# displayBoard-v1.net
KiCad netlist of a schematic drawn in EAGLE
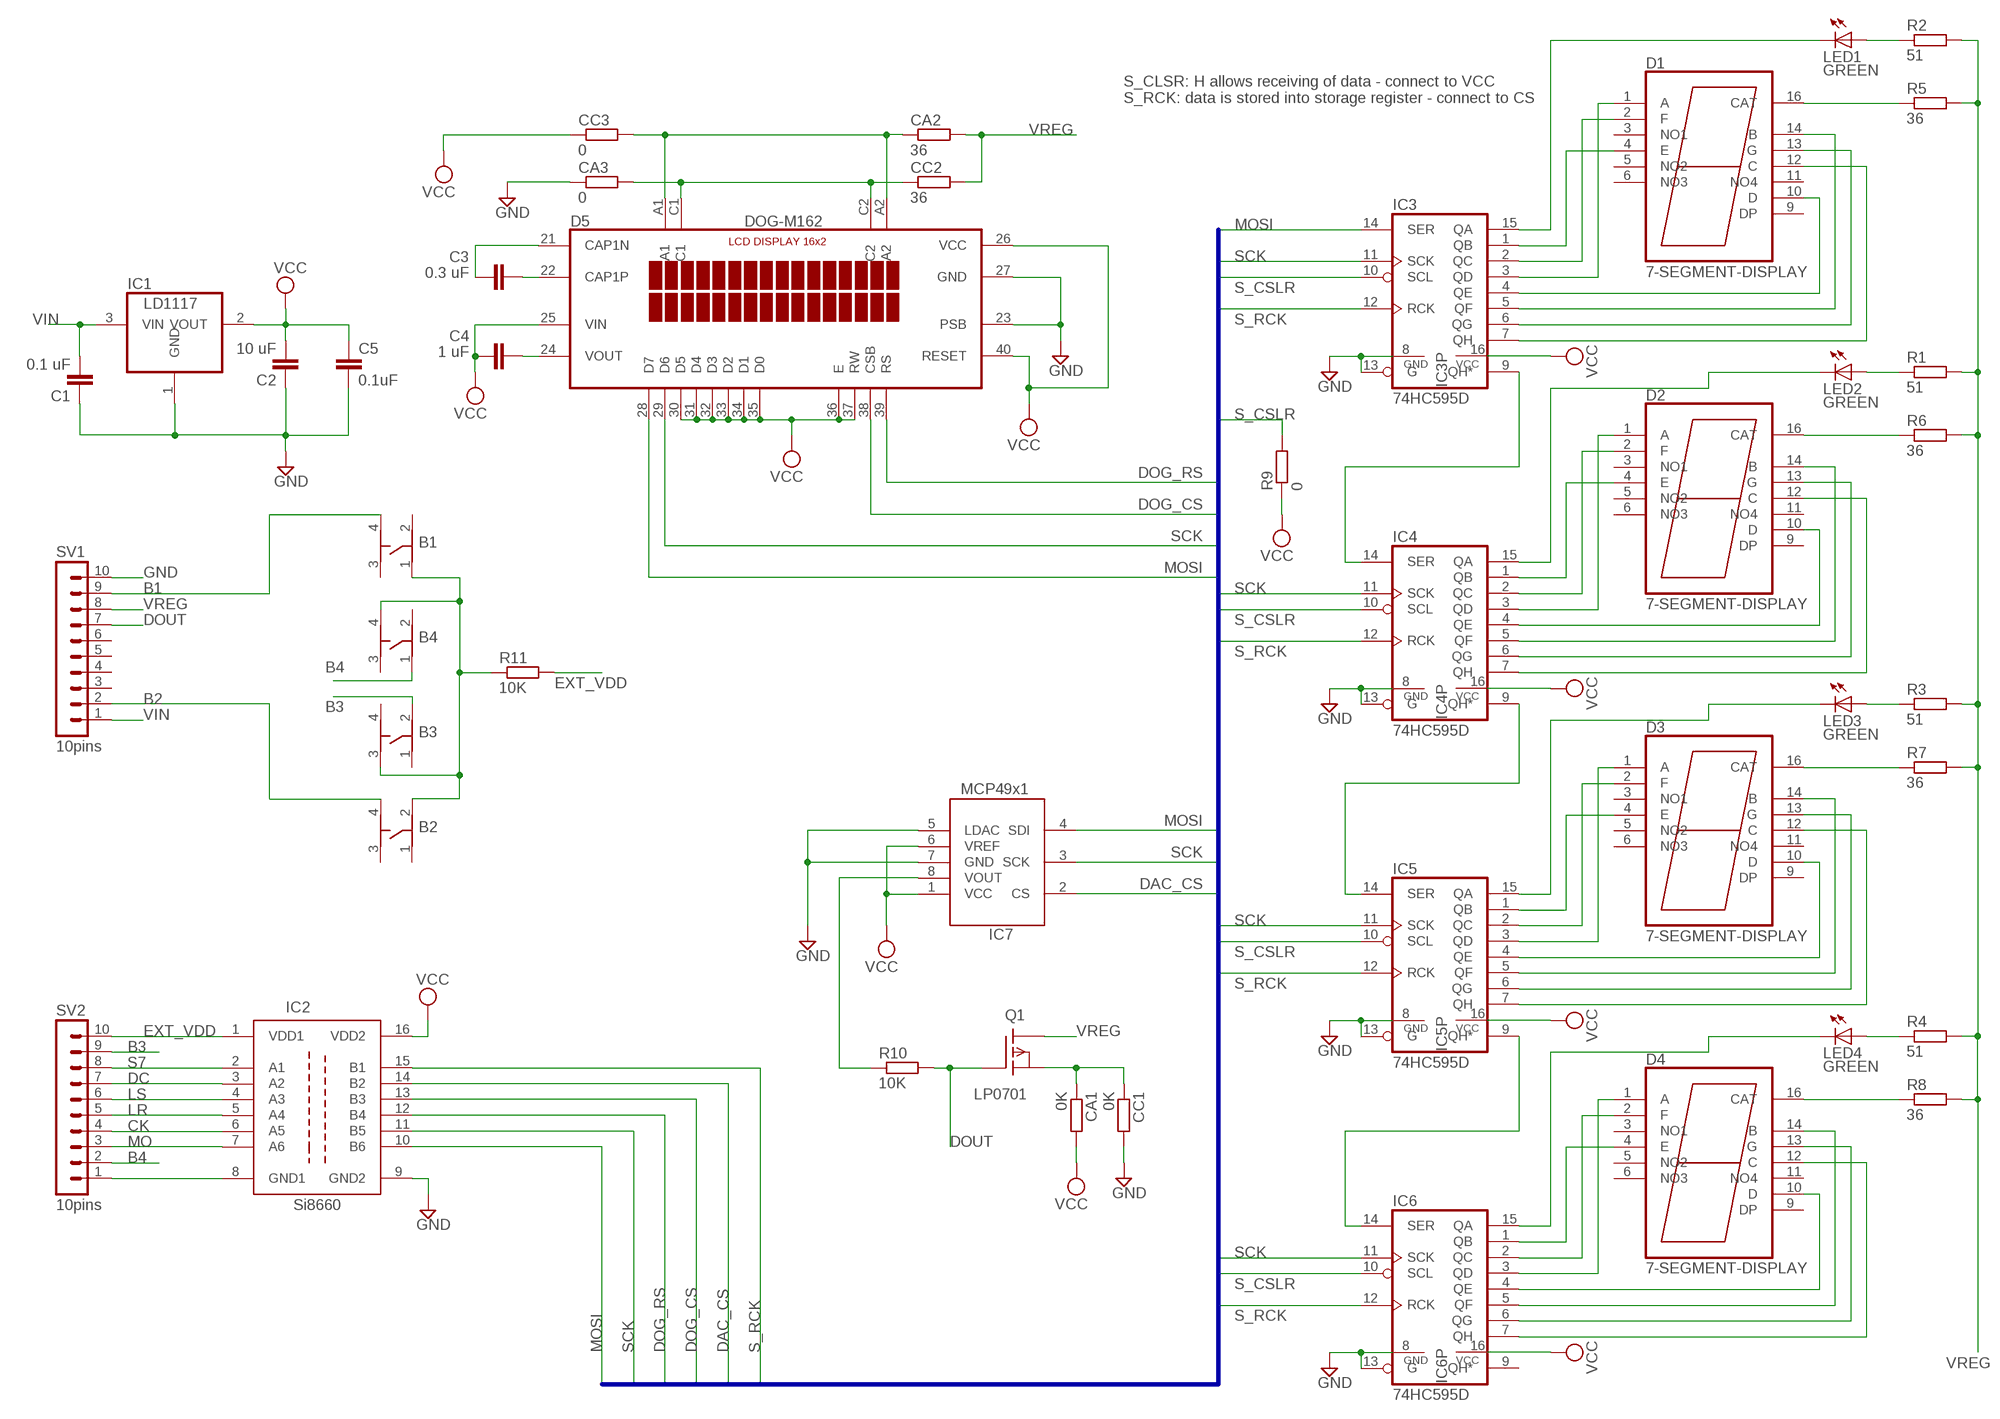
[diagram p0: schematic, sheet 1]

(export (version "E")
  (design (tool "Eeschema 10.0.6"))
  (components
    (comp (ref "B1")
      (value "BUTTON-D6X")
      (footprint "eagle-import:BUTTON-D6X")
      (libsource (lib "eagle-import") (part "BUTTON-D6X"))
    )
    (comp (ref "B2")
      (value "BUTTON-D6X")
      (footprint "eagle-import:BUTTON-D6X")
      (libsource (lib "eagle-import") (part "BUTTON-D6X"))
    )
    (comp (ref "B3")
      (value "BUTTON-D6X")
      (footprint "eagle-import:BUTTON-D6X")
      (libsource (lib "eagle-import") (part "BUTTON-D6X"))
    )
    (comp (ref "B4")
      (value "BUTTON-D6X")
      (footprint "eagle-import:BUTTON-D6X")
      (libsource (lib "eagle-import") (part "BUTTON-D6X"))
    )
    (comp (ref "C1")
      (value "0.1 uF")
      (footprint "eagle-import:C1206")
      (libsource (lib "eagle-import") (part "C-EUC1206"))
    )
    (comp (ref "C2")
      (value "10 uF")
      (footprint "eagle-import:C1206")
      (libsource (lib "eagle-import") (part "C-EUC1206"))
    )
    (comp (ref "C3")
      (value "0.3 uF")
      (footprint "eagle-import:C1206")
      (libsource (lib "eagle-import") (part "C-EUC1206"))
    )
    (comp (ref "C4")
      (value "1 uF")
      (footprint "eagle-import:C1206")
      (libsource (lib "eagle-import") (part "C-EUC1206"))
    )
    (comp (ref "C5")
      (value "0.1uF")
      (footprint "eagle-import:C1206")
      (libsource (lib "eagle-import") (part "C-EUC1206"))
    )
    (comp (ref "CA1")
      (value "0K")
      (footprint "eagle-import:R1206")
      (libsource (lib "eagle-import") (part "R-EU_R1206"))
    )
    (comp (ref "CA2")
      (value "36")
      (footprint "eagle-import:R1206")
      (libsource (lib "eagle-import") (part "R-EU_R1206"))
    )
    (comp (ref "CA3")
      (value "0")
      (footprint "eagle-import:R1206")
      (libsource (lib "eagle-import") (part "R-EU_R1206"))
    )
    (comp (ref "CC1")
      (value "0K")
      (footprint "eagle-import:R1206")
      (libsource (lib "eagle-import") (part "R-EU_R1206"))
    )
    (comp (ref "CC2")
      (value "36")
      (footprint "eagle-import:R1206")
      (libsource (lib "eagle-import") (part "R-EU_R1206"))
    )
    (comp (ref "CC3")
      (value "0")
      (footprint "eagle-import:R1206")
      (libsource (lib "eagle-import") (part "R-EU_R1206"))
    )
    (comp (ref "D1")
      (value "7-SEGMENT-DISPLAY")
      (footprint "eagle-import:LDS-A812")
      (libsource (lib "eagle-import") (part "7-SEGMENT-DISPLAY"))
    )
    (comp (ref "D2")
      (value "7-SEGMENT-DISPLAY")
      (footprint "eagle-import:LDS-A812")
      (libsource (lib "eagle-import") (part "7-SEGMENT-DISPLAY"))
    )
    (comp (ref "D3")
      (value "7-SEGMENT-DISPLAY")
      (footprint "eagle-import:LDS-A812")
      (libsource (lib "eagle-import") (part "7-SEGMENT-DISPLAY"))
    )
    (comp (ref "D4")
      (value "7-SEGMENT-DISPLAY")
      (footprint "eagle-import:LDS-A812")
      (libsource (lib "eagle-import") (part "7-SEGMENT-DISPLAY"))
    )
    (comp (ref "D5")
      (value "DOG-M162")
      (footprint "eagle-import:DOGM162")
      (libsource (lib "eagle-import") (part "DOG-M162"))
    )
    (comp (ref "IC1")
      (value "LD1117")
      (footprint "eagle-import:SOT223")
      (fields (field (name "MPN") "REG1117"))
      (libsource (lib "eagle-import") (part "REG1117"))
    )
    (comp (ref "IC2")
      (value "SI-8660")
      (footprint "eagle-import:SOP-16")
      (libsource (lib "eagle-import") (part "SI-8660"))
    )
    (comp (ref "IC3")
      (value "74HC595D")
      (footprint "eagle-import:SO16")
      (libsource (lib "eagle-import") (part "74595DHC"))
    )
    (comp (ref "IC4")
      (value "74HC595D")
      (footprint "eagle-import:SO16")
      (libsource (lib "eagle-import") (part "74595DHC"))
    )
    (comp (ref "IC5")
      (value "74HC595D")
      (footprint "eagle-import:SO16")
      (libsource (lib "eagle-import") (part "74595DHC"))
    )
    (comp (ref "IC6")
      (value "74HC595D")
      (footprint "eagle-import:SO16")
      (libsource (lib "eagle-import") (part "74595DHC"))
    )
    (comp (ref "IC7")
      (value "MCP4921")
      (footprint "eagle-import:MSOP-8")
      (libsource (lib "eagle-import") (part "MCP4901"))
    )
    (comp (ref "LED1")
      (value "GREEN")
      (footprint "eagle-import:LED3MM")
      (libsource (lib "eagle-import") (part "LED3MM"))
    )
    (comp (ref "LED2")
      (value "GREEN")
      (footprint "eagle-import:LED3MM")
      (libsource (lib "eagle-import") (part "LED3MM"))
    )
    (comp (ref "LED3")
      (value "GREEN")
      (footprint "eagle-import:LED3MM")
      (libsource (lib "eagle-import") (part "LED3MM"))
    )
    (comp (ref "LED4")
      (value "GREEN")
      (footprint "eagle-import:LED3MM")
      (libsource (lib "eagle-import") (part "LED3MM"))
    )
    (comp (ref "Q1")
      (value "LP0701")
      (footprint "eagle-import:TO-92")
      (libsource (lib "eagle-import") (part "LP0701N3"))
    )
    (comp (ref "R1")
      (value "51")
      (footprint "eagle-import:R1206")
      (libsource (lib "eagle-import") (part "R-EU_R1206"))
    )
    (comp (ref "R2")
      (value "51")
      (footprint "eagle-import:R1206")
      (libsource (lib "eagle-import") (part "R-EU_R1206"))
    )
    (comp (ref "R3")
      (value "51")
      (footprint "eagle-import:R1206")
      (libsource (lib "eagle-import") (part "R-EU_R1206"))
    )
    (comp (ref "R4")
      (value "51")
      (footprint "eagle-import:R1206")
      (libsource (lib "eagle-import") (part "R-EU_R1206"))
    )
    (comp (ref "R5")
      (value "36")
      (footprint "eagle-import:R1206")
      (libsource (lib "eagle-import") (part "R-EU_R1206"))
    )
    (comp (ref "R6")
      (value "36")
      (footprint "eagle-import:R1206")
      (libsource (lib "eagle-import") (part "R-EU_R1206"))
    )
    (comp (ref "R7")
      (value "36")
      (footprint "eagle-import:R1206")
      (libsource (lib "eagle-import") (part "R-EU_R1206"))
    )
    (comp (ref "R8")
      (value "36")
      (footprint "eagle-import:R1206")
      (libsource (lib "eagle-import") (part "R-EU_R1206"))
    )
    (comp (ref "R9")
      (value "0")
      (footprint "eagle-import:R1206")
      (libsource (lib "eagle-import") (part "R-EU_R1206"))
    )
    (comp (ref "R10")
      (value "10K")
      (footprint "eagle-import:R1206")
      (libsource (lib "eagle-import") (part "R-EU_R1206"))
    )
    (comp (ref "R11")
      (value "10K")
      (footprint "eagle-import:R1206")
      (libsource (lib "eagle-import") (part "R-EU_R1206"))
    )
    (comp (ref "SV1")
      (value "10pins")
      (footprint "eagle-import:MA10-1")
      (libsource (lib "eagle-import") (part "MA10-1"))
    )
    (comp (ref "SV2")
      (value "10pins")
      (footprint "eagle-import:MA10-1")
      (libsource (lib "eagle-import") (part "MA10-1"))
    )
  )
  (nets
    (net (code "1") (name "/B1") (class "Default")
      (node (ref "B1") (pin "4") (pinfunction "4_4") (pintype "bidirectional"))
      (node (ref "SV1") (pin "9") (pinfunction "9_9") (pintype "passive"))
    )
    (net (code "2") (name "/B2") (class "Default")
      (node (ref "B2") (pin "4") (pinfunction "4_4") (pintype "bidirectional"))
      (node (ref "SV1") (pin "2") (pinfunction "2_2") (pintype "passive"))
    )
    (net (code "3") (name "/B3") (class "Default")
      (node (ref "B3") (pin "2") (pinfunction "2_2") (pintype "bidirectional"))
      (node (ref "SV2") (pin "9") (pinfunction "9_9") (pintype "passive"))
    )
    (net (code "4") (name "/B4") (class "Default")
      (node (ref "B4") (pin "1") (pinfunction "1_1") (pintype "bidirectional"))
      (node (ref "SV2") (pin "2") (pinfunction "2_2") (pintype "passive"))
    )
    (net (code "5") (name "/CK") (class "Default")
      (node (ref "IC2") (pin "6") (pinfunction "A5_6") (pintype "bidirectional"))
      (node (ref "SV2") (pin "4") (pinfunction "4_4") (pintype "passive"))
    )
    (net (code "6") (name "/DAC_CS") (class "Default")
      (node (ref "IC2") (pin "14") (pinfunction "B2_14") (pintype "bidirectional"))
      (node (ref "IC7") (pin "2") (pinfunction "CS_2") (pintype "bidirectional"))
    )
    (net (code "7") (name "/DC") (class "Default")
      (node (ref "IC2") (pin "3") (pinfunction "A2_3") (pintype "bidirectional"))
      (node (ref "SV2") (pin "7") (pinfunction "7_7") (pintype "passive"))
    )
    (net (code "8") (name "/DOG_CS") (class "Default")
      (node (ref "D5") (pin "38") (pinfunction "CSB_38") (pintype "bidirectional"))
      (node (ref "IC2") (pin "13") (pinfunction "B3_13") (pintype "bidirectional"))
    )
    (net (code "9") (name "/DOG_RS") (class "Default")
      (node (ref "D5") (pin "39") (pinfunction "RS_39") (pintype "bidirectional"))
      (node (ref "IC2") (pin "12") (pinfunction "B4_12") (pintype "bidirectional"))
    )
    (net (code "10") (name "/DOUT") (class "Default")
      (node (ref "Q1") (pin "2") (pinfunction "G_2") (pintype "passive"))
      (node (ref "R10") (pin "2") (pinfunction "2_2") (pintype "passive"))
      (node (ref "SV1") (pin "7") (pinfunction "7_7") (pintype "passive"))
    )
    (net (code "11") (name "/EXT_VDD") (class "Default")
      (node (ref "IC2") (pin "1") (pinfunction "VDD1_1") (pintype "bidirectional"))
      (node (ref "R11") (pin "2") (pinfunction "2_2") (pintype "passive"))
      (node (ref "SV2") (pin "10") (pinfunction "10_10") (pintype "passive"))
    )
    (net (code "12") (name "/LR") (class "Default")
      (node (ref "IC2") (pin "5") (pinfunction "A4_5") (pintype "bidirectional"))
      (node (ref "SV2") (pin "5") (pinfunction "5_5") (pintype "passive"))
    )
    (net (code "13") (name "/LS") (class "Default")
      (node (ref "IC2") (pin "4") (pinfunction "A3_4") (pintype "bidirectional"))
      (node (ref "SV2") (pin "6") (pinfunction "6_6") (pintype "passive"))
    )
    (net (code "14") (name "/MO") (class "Default")
      (node (ref "IC2") (pin "7") (pinfunction "A6_7") (pintype "bidirectional"))
      (node (ref "SV2") (pin "3") (pinfunction "3_3") (pintype "passive"))
    )
    (net (code "15") (name "/MOSI") (class "Default")
      (node (ref "D5") (pin "28") (pinfunction "D7_28") (pintype "bidirectional"))
      (node (ref "IC2") (pin "10") (pinfunction "B6_10") (pintype "bidirectional"))
      (node (ref "IC3") (pin "14") (pinfunction "SER_14") (pintype "input"))
      (node (ref "IC7") (pin "4") (pinfunction "SDI_4") (pintype "bidirectional"))
    )
    (net (code "16") (name "/S7") (class "Default")
      (node (ref "IC2") (pin "2") (pinfunction "A1_2") (pintype "bidirectional"))
      (node (ref "SV2") (pin "8") (pinfunction "8_8") (pintype "passive"))
    )
    (net (code "17") (name "/SCK") (class "Default")
      (node (ref "D5") (pin "29") (pinfunction "D6_29") (pintype "bidirectional"))
      (node (ref "IC2") (pin "11") (pinfunction "B5_11") (pintype "bidirectional"))
      (node (ref "IC3") (pin "11") (pinfunction "SCK_11") (pintype "input"))
      (node (ref "IC4") (pin "11") (pinfunction "SCK_11") (pintype "input"))
      (node (ref "IC5") (pin "11") (pinfunction "SCK_11") (pintype "input"))
      (node (ref "IC6") (pin "11") (pinfunction "SCK_11") (pintype "input"))
      (node (ref "IC7") (pin "3") (pinfunction "SCK_3") (pintype "bidirectional"))
    )
    (net (code "18") (name "/S_CSLR") (class "Default")
      (node (ref "IC3") (pin "10") (pinfunction "SCL_10") (pintype "input"))
      (node (ref "IC4") (pin "10") (pinfunction "SCL_10") (pintype "input"))
      (node (ref "IC5") (pin "10") (pinfunction "SCL_10") (pintype "input"))
      (node (ref "IC6") (pin "10") (pinfunction "SCL_10") (pintype "input"))
      (node (ref "R9") (pin "2") (pinfunction "2_2") (pintype "passive"))
    )
    (net (code "19") (name "/S_RCK") (class "Default")
      (node (ref "IC2") (pin "15") (pinfunction "B1_15") (pintype "bidirectional"))
      (node (ref "IC3") (pin "12") (pinfunction "RCK_12") (pintype "input"))
      (node (ref "IC4") (pin "12") (pinfunction "RCK_12") (pintype "input"))
      (node (ref "IC5") (pin "12") (pinfunction "RCK_12") (pintype "input"))
      (node (ref "IC6") (pin "12") (pinfunction "RCK_12") (pintype "input"))
    )
    (net (code "20") (name "/VIN") (class "Default")
      (node (ref "C1") (pin "2") (pinfunction "2_2") (pintype "passive"))
      (node (ref "IC1") (pin "3") (pinfunction "VIN_3") (pintype "input"))
      (node (ref "SV1") (pin "1") (pinfunction "1_1") (pintype "passive"))
    )
    (net (code "21") (name "/VREG") (class "Default")
      (node (ref "CA2") (pin "2") (pinfunction "2_2") (pintype "passive"))
      (node (ref "CC2") (pin "2") (pinfunction "2_2") (pintype "passive"))
      (node (ref "Q1") (pin "3") (pinfunction "D_3") (pintype "passive"))
      (node (ref "R1") (pin "2") (pinfunction "2_2") (pintype "passive"))
      (node (ref "R2") (pin "2") (pinfunction "2_2") (pintype "passive"))
      (node (ref "R3") (pin "2") (pinfunction "2_2") (pintype "passive"))
      (node (ref "R4") (pin "2") (pinfunction "2_2") (pintype "passive"))
      (node (ref "R5") (pin "2") (pinfunction "2_2") (pintype "passive"))
      (node (ref "R6") (pin "2") (pinfunction "2_2") (pintype "passive"))
      (node (ref "R7") (pin "2") (pinfunction "2_2") (pintype "passive"))
      (node (ref "R8") (pin "2") (pinfunction "2_2") (pintype "passive"))
      (node (ref "SV1") (pin "8") (pinfunction "8_8") (pintype "passive"))
    )
    (net (code "22") (name "GND") (class "Default")
      (node (ref "C1") (pin "1") (pinfunction "1_1") (pintype "passive"))
      (node (ref "C2") (pin "1") (pinfunction "1_1") (pintype "passive"))
      (node (ref "C5") (pin "2") (pinfunction "2_2") (pintype "passive"))
      (node (ref "CA3") (pin "1") (pinfunction "1_1") (pintype "passive"))
      (node (ref "CC1") (pin "2") (pinfunction "2_2") (pintype "passive"))
      (node (ref "D5") (pin "23") (pinfunction "PSB_23") (pintype "bidirectional"))
      (node (ref "D5") (pin "27") (pinfunction "GND_27") (pintype "power_in"))
      (node (ref "IC1") (pin "1") (pinfunction "GND_1") (pintype "power_in"))
      (node (ref "IC2") (pin "9") (pinfunction "GND2_9") (pintype "bidirectional"))
      (node (ref "IC3") (pin "13") (pinfunction "G_13") (pintype "input"))
      (node (ref "IC3") (pin "8") (pinfunction "GND_8") (pintype "power_in"))
      (node (ref "IC4") (pin "13") (pinfunction "G_13") (pintype "input"))
      (node (ref "IC4") (pin "8") (pinfunction "GND_8") (pintype "power_in"))
      (node (ref "IC5") (pin "13") (pinfunction "G_13") (pintype "input"))
      (node (ref "IC5") (pin "8") (pinfunction "GND_8") (pintype "power_in"))
      (node (ref "IC6") (pin "13") (pinfunction "G_13") (pintype "input"))
      (node (ref "IC6") (pin "8") (pinfunction "GND_8") (pintype "power_in"))
      (node (ref "IC7") (pin "5") (pinfunction "LDAC_5") (pintype "bidirectional"))
      (node (ref "IC7") (pin "7") (pinfunction "GND_7") (pintype "power_in"))
      (node (ref "SV1") (pin "10") (pinfunction "10_10") (pintype "passive"))
    )
    (net (code "23") (name "Net-(B1-Pad1)") (class "Default")
      (node (ref "B1") (pin "1") (pinfunction "1_1") (pintype "bidirectional"))
      (node (ref "B2") (pin "2") (pinfunction "2_2") (pintype "bidirectional"))
      (node (ref "B3") (pin "3") (pinfunction "3_3") (pintype "bidirectional"))
      (node (ref "B4") (pin "4") (pinfunction "4_4") (pintype "bidirectional"))
      (node (ref "R11") (pin "1") (pinfunction "1_1") (pintype "passive"))
    )
    (net (code "24") (name "Net-(CA2-Pad1)") (class "Default")
      (node (ref "CA2") (pin "1") (pinfunction "1_1") (pintype "passive"))
      (node (ref "CC3") (pin "2") (pinfunction "2_2") (pintype "passive"))
      (node (ref "D5") (pin "A1") (pinfunction "A1_A1") (pintype "bidirectional"))
      (node (ref "D5") (pin "A2") (pinfunction "A2_A2") (pintype "bidirectional"))
    )
    (net (code "25") (name "Net-(CA3-Pad2)") (class "Default")
      (node (ref "CA3") (pin "2") (pinfunction "2_2") (pintype "passive"))
      (node (ref "CC2") (pin "1") (pinfunction "1_1") (pintype "passive"))
      (node (ref "D5") (pin "C1") (pinfunction "C1_C1") (pintype "bidirectional"))
      (node (ref "D5") (pin "C2") (pinfunction "C2_C2") (pintype "bidirectional"))
    )
    (net (code "26") (name "Net-(D1-A)") (class "Default")
      (node (ref "D1") (pin "1") (pinfunction "A_1") (pintype "input"))
      (node (ref "IC3") (pin "3") (pinfunction "QD_3") (pintype "tri_state"))
    )
    (net (code "27") (name "Net-(D1-B)") (class "Default")
      (node (ref "D1") (pin "14") (pinfunction "B_14") (pintype "input"))
      (node (ref "IC3") (pin "5") (pinfunction "QF_5") (pintype "tri_state"))
    )
    (net (code "28") (name "Net-(D1-C)") (class "Default")
      (node (ref "D1") (pin "12") (pinfunction "C_12") (pintype "input"))
      (node (ref "IC3") (pin "7") (pinfunction "QH_7") (pintype "tri_state"))
    )
    (net (code "29") (name "Net-(D1-CAT)") (class "Default")
      (node (ref "D1") (pin "16") (pinfunction "CAT_16") (pintype "bidirectional"))
      (node (ref "R5") (pin "1") (pinfunction "1_1") (pintype "passive"))
    )
    (net (code "30") (name "Net-(D1-D)") (class "Default")
      (node (ref "D1") (pin "10") (pinfunction "D_10") (pintype "input"))
      (node (ref "IC3") (pin "4") (pinfunction "QE_4") (pintype "tri_state"))
    )
    (net (code "31") (name "Net-(D1-E)") (class "Default")
      (node (ref "D1") (pin "4") (pinfunction "E_4") (pintype "input"))
      (node (ref "IC3") (pin "1") (pinfunction "QB_1") (pintype "tri_state"))
    )
    (net (code "32") (name "Net-(D1-F)") (class "Default")
      (node (ref "D1") (pin "2") (pinfunction "F_2") (pintype "input"))
      (node (ref "IC3") (pin "2") (pinfunction "QC_2") (pintype "tri_state"))
    )
    (net (code "33") (name "Net-(D1-G)") (class "Default")
      (node (ref "D1") (pin "13") (pinfunction "G_13") (pintype "input"))
      (node (ref "IC3") (pin "6") (pinfunction "QG_6") (pintype "tri_state"))
    )
    (net (code "34") (name "Net-(D2-A)") (class "Default")
      (node (ref "D2") (pin "1") (pinfunction "A_1") (pintype "input"))
      (node (ref "IC4") (pin "3") (pinfunction "QD_3") (pintype "tri_state"))
    )
    (net (code "35") (name "Net-(D2-B)") (class "Default")
      (node (ref "D2") (pin "14") (pinfunction "B_14") (pintype "input"))
      (node (ref "IC4") (pin "5") (pinfunction "QF_5") (pintype "tri_state"))
    )
    (net (code "36") (name "Net-(D2-C)") (class "Default")
      (node (ref "D2") (pin "12") (pinfunction "C_12") (pintype "input"))
      (node (ref "IC4") (pin "7") (pinfunction "QH_7") (pintype "tri_state"))
    )
    (net (code "37") (name "Net-(D2-CAT)") (class "Default")
      (node (ref "D2") (pin "16") (pinfunction "CAT_16") (pintype "bidirectional"))
      (node (ref "R6") (pin "1") (pinfunction "1_1") (pintype "passive"))
    )
    (net (code "38") (name "Net-(D2-D)") (class "Default")
      (node (ref "D2") (pin "10") (pinfunction "D_10") (pintype "input"))
      (node (ref "IC4") (pin "4") (pinfunction "QE_4") (pintype "tri_state"))
    )
    (net (code "39") (name "Net-(D2-E)") (class "Default")
      (node (ref "D2") (pin "4") (pinfunction "E_4") (pintype "input"))
      (node (ref "IC4") (pin "1") (pinfunction "QB_1") (pintype "tri_state"))
    )
    (net (code "40") (name "Net-(D2-F)") (class "Default")
      (node (ref "D2") (pin "2") (pinfunction "F_2") (pintype "input"))
      (node (ref "IC4") (pin "2") (pinfunction "QC_2") (pintype "tri_state"))
    )
    (net (code "41") (name "Net-(D2-G)") (class "Default")
      (node (ref "D2") (pin "13") (pinfunction "G_13") (pintype "input"))
      (node (ref "IC4") (pin "6") (pinfunction "QG_6") (pintype "tri_state"))
    )
    (net (code "42") (name "Net-(D3-A)") (class "Default")
      (node (ref "D3") (pin "1") (pinfunction "A_1") (pintype "input"))
      (node (ref "IC5") (pin "3") (pinfunction "QD_3") (pintype "tri_state"))
    )
    (net (code "43") (name "Net-(D3-B)") (class "Default")
      (node (ref "D3") (pin "14") (pinfunction "B_14") (pintype "input"))
      (node (ref "IC5") (pin "5") (pinfunction "QF_5") (pintype "tri_state"))
    )
    (net (code "44") (name "Net-(D3-C)") (class "Default")
      (node (ref "D3") (pin "12") (pinfunction "C_12") (pintype "input"))
      (node (ref "IC5") (pin "7") (pinfunction "QH_7") (pintype "tri_state"))
    )
    (net (code "45") (name "Net-(D3-CAT)") (class "Default")
      (node (ref "D3") (pin "16") (pinfunction "CAT_16") (pintype "bidirectional"))
      (node (ref "R7") (pin "1") (pinfunction "1_1") (pintype "passive"))
    )
    (net (code "46") (name "Net-(D3-D)") (class "Default")
      (node (ref "D3") (pin "10") (pinfunction "D_10") (pintype "input"))
      (node (ref "IC5") (pin "4") (pinfunction "QE_4") (pintype "tri_state"))
    )
    (net (code "47") (name "Net-(D3-E)") (class "Default")
      (node (ref "D3") (pin "4") (pinfunction "E_4") (pintype "input"))
      (node (ref "IC5") (pin "1") (pinfunction "QB_1") (pintype "tri_state"))
    )
    (net (code "48") (name "Net-(D3-F)") (class "Default")
      (node (ref "D3") (pin "2") (pinfunction "F_2") (pintype "input"))
      (node (ref "IC5") (pin "2") (pinfunction "QC_2") (pintype "tri_state"))
    )
    (net (code "49") (name "Net-(D3-G)") (class "Default")
      (node (ref "D3") (pin "13") (pinfunction "G_13") (pintype "input"))
      (node (ref "IC5") (pin "6") (pinfunction "QG_6") (pintype "tri_state"))
    )
    (net (code "50") (name "Net-(D4-A)") (class "Default")
      (node (ref "D4") (pin "1") (pinfunction "A_1") (pintype "input"))
      (node (ref "IC6") (pin "3") (pinfunction "QD_3") (pintype "tri_state"))
    )
    (net (code "51") (name "Net-(D4-B)") (class "Default")
      (node (ref "D4") (pin "14") (pinfunction "B_14") (pintype "input"))
      (node (ref "IC6") (pin "5") (pinfunction "QF_5") (pintype "tri_state"))
    )
    (net (code "52") (name "Net-(D4-C)") (class "Default")
      (node (ref "D4") (pin "12") (pinfunction "C_12") (pintype "input"))
      (node (ref "IC6") (pin "7") (pinfunction "QH_7") (pintype "tri_state"))
    )
    (net (code "53") (name "Net-(D4-CAT)") (class "Default")
      (node (ref "D4") (pin "16") (pinfunction "CAT_16") (pintype "bidirectional"))
      (node (ref "R8") (pin "1") (pinfunction "1_1") (pintype "passive"))
    )
    (net (code "54") (name "Net-(D4-D)") (class "Default")
      (node (ref "D4") (pin "10") (pinfunction "D_10") (pintype "input"))
      (node (ref "IC6") (pin "4") (pinfunction "QE_4") (pintype "tri_state"))
    )
    (net (code "55") (name "Net-(D4-E)") (class "Default")
      (node (ref "D4") (pin "4") (pinfunction "E_4") (pintype "input"))
      (node (ref "IC6") (pin "1") (pinfunction "QB_1") (pintype "tri_state"))
    )
    (net (code "56") (name "Net-(D4-F)") (class "Default")
      (node (ref "D4") (pin "2") (pinfunction "F_2") (pintype "input"))
      (node (ref "IC6") (pin "2") (pinfunction "QC_2") (pintype "tri_state"))
    )
    (net (code "57") (name "Net-(D4-G)") (class "Default")
      (node (ref "D4") (pin "13") (pinfunction "G_13") (pintype "input"))
      (node (ref "IC6") (pin "6") (pinfunction "QG_6") (pintype "tri_state"))
    )
    (net (code "58") (name "Net-(D5-CAP1N)") (class "Default")
      (node (ref "C3") (pin "1") (pinfunction "1_1") (pintype "passive"))
      (node (ref "D5") (pin "21") (pinfunction "CAP1N_21") (pintype "bidirectional"))
    )
    (net (code "59") (name "Net-(D5-CAP1P)") (class "Default")
      (node (ref "C3") (pin "2") (pinfunction "2_2") (pintype "passive"))
      (node (ref "D5") (pin "22") (pinfunction "CAP1P_22") (pintype "bidirectional"))
    )
    (net (code "60") (name "Net-(D5-VOUT)") (class "Default")
      (node (ref "C4") (pin "1") (pinfunction "1_1") (pintype "passive"))
      (node (ref "D5") (pin "24") (pinfunction "VOUT_24") (pintype "bidirectional"))
    )
    (net (code "61") (name "Net-(IC2-GND1)") (class "Default")
      (node (ref "IC2") (pin "8") (pinfunction "GND1_8") (pintype "bidirectional"))
      (node (ref "SV2") (pin "1") (pinfunction "1_1") (pintype "passive"))
    )
    (net (code "62") (name "Net-(IC3A-QA)") (class "Default")
      (node (ref "IC3") (pin "15") (pinfunction "QA_15") (pintype "tri_state"))
      (node (ref "LED1") (pin "K") (pinfunction "C_K") (pintype "passive"))
    )
    (net (code "63") (name "Net-(IC3A-QH*)") (class "Default")
      (node (ref "IC3") (pin "9") (pinfunction "QH*_9") (pintype "tri_state"))
      (node (ref "IC4") (pin "14") (pinfunction "SER_14") (pintype "input"))
    )
    (net (code "64") (name "Net-(IC4A-QA)") (class "Default")
      (node (ref "IC4") (pin "15") (pinfunction "QA_15") (pintype "tri_state"))
      (node (ref "LED2") (pin "K") (pinfunction "C_K") (pintype "passive"))
    )
    (net (code "65") (name "Net-(IC4A-QH*)") (class "Default")
      (node (ref "IC4") (pin "9") (pinfunction "QH*_9") (pintype "tri_state"))
      (node (ref "IC5") (pin "14") (pinfunction "SER_14") (pintype "input"))
    )
    (net (code "66") (name "Net-(IC5A-QA)") (class "Default")
      (node (ref "IC5") (pin "15") (pinfunction "QA_15") (pintype "tri_state"))
      (node (ref "LED3") (pin "K") (pinfunction "C_K") (pintype "passive"))
    )
    (net (code "67") (name "Net-(IC5A-QH*)") (class "Default")
      (node (ref "IC5") (pin "9") (pinfunction "QH*_9") (pintype "tri_state"))
      (node (ref "IC6") (pin "14") (pinfunction "SER_14") (pintype "input"))
    )
    (net (code "68") (name "Net-(IC6A-QA)") (class "Default")
      (node (ref "IC6") (pin "15") (pinfunction "QA_15") (pintype "tri_state"))
      (node (ref "LED4") (pin "K") (pinfunction "C_K") (pintype "passive"))
    )
    (net (code "69") (name "Net-(IC7-VOUT)") (class "Default")
      (node (ref "IC7") (pin "8") (pinfunction "VOUT_8") (pintype "bidirectional"))
      (node (ref "R10") (pin "1") (pinfunction "1_1") (pintype "passive"))
    )
    (net (code "70") (name "Net-(LED1-PadA)") (class "Default")
      (node (ref "LED1") (pin "A") (pinfunction "A_A") (pintype "passive"))
      (node (ref "R2") (pin "1") (pinfunction "1_1") (pintype "passive"))
    )
    (net (code "71") (name "Net-(LED2-PadA)") (class "Default")
      (node (ref "LED2") (pin "A") (pinfunction "A_A") (pintype "passive"))
      (node (ref "R1") (pin "1") (pinfunction "1_1") (pintype "passive"))
    )
    (net (code "72") (name "Net-(LED3-PadA)") (class "Default")
      (node (ref "LED3") (pin "A") (pinfunction "A_A") (pintype "passive"))
      (node (ref "R3") (pin "1") (pinfunction "1_1") (pintype "passive"))
    )
    (net (code "73") (name "Net-(LED4-PadA)") (class "Default")
      (node (ref "LED4") (pin "A") (pinfunction "A_A") (pintype "passive"))
      (node (ref "R4") (pin "1") (pinfunction "1_1") (pintype "passive"))
    )
    (net (code "74") (name "Net-(Q1-S)") (class "Default")
      (node (ref "CA1") (pin "1") (pinfunction "1_1") (pintype "passive"))
      (node (ref "CC1") (pin "1") (pinfunction "1_1") (pintype "passive"))
      (node (ref "Q1") (pin "1") (pinfunction "S_1") (pintype "passive"))
    )
    (net (code "75") (name "VCC") (class "Default")
      (node (ref "C2") (pin "2") (pinfunction "2_2") (pintype "passive"))
      (node (ref "C4") (pin "2") (pinfunction "2_2") (pintype "passive"))
      (node (ref "C5") (pin "1") (pinfunction "1_1") (pintype "passive"))
      (node (ref "CA1") (pin "2") (pinfunction "2_2") (pintype "passive"))
      (node (ref "CC3") (pin "1") (pinfunction "1_1") (pintype "passive"))
      (node (ref "D5") (pin "25") (pinfunction "VIN_25") (pintype "bidirectional"))
      (node (ref "D5") (pin "26") (pinfunction "VCC_26") (pintype "power_in"))
      (node (ref "D5") (pin "30") (pinfunction "D5_30") (pintype "bidirectional"))
      (node (ref "D5") (pin "31") (pinfunction "D4_31") (pintype "bidirectional"))
      (node (ref "D5") (pin "32") (pinfunction "D3_32") (pintype "bidirectional"))
      (node (ref "D5") (pin "33") (pinfunction "D2_33") (pintype "bidirectional"))
      (node (ref "D5") (pin "34") (pinfunction "D1_34") (pintype "bidirectional"))
      (node (ref "D5") (pin "35") (pinfunction "D0_35") (pintype "bidirectional"))
      (node (ref "D5") (pin "36") (pinfunction "E_36") (pintype "bidirectional"))
      (node (ref "D5") (pin "37") (pinfunction "RW_37") (pintype "bidirectional"))
      (node (ref "D5") (pin "40") (pinfunction "RESET_40") (pintype "bidirectional"))
      (node (ref "IC1") (pin "2") (pinfunction "VOUT_2") (pintype "power_in"))
      (node (ref "IC2") (pin "16") (pinfunction "VDD2_16") (pintype "bidirectional"))
      (node (ref "IC3") (pin "16") (pinfunction "VCC_16") (pintype "power_in"))
      (node (ref "IC4") (pin "16") (pinfunction "VCC_16") (pintype "power_in"))
      (node (ref "IC5") (pin "16") (pinfunction "VCC_16") (pintype "power_in"))
      (node (ref "IC6") (pin "16") (pinfunction "VCC_16") (pintype "power_in"))
      (node (ref "IC7") (pin "1") (pinfunction "VCC_1") (pintype "power_in"))
      (node (ref "IC7") (pin "6") (pinfunction "VREF_6") (pintype "bidirectional"))
      (node (ref "R9") (pin "1") (pinfunction "1_1") (pintype "passive"))
    )
    (net (code "76") (name "unconnected-(B1-Pad2)") (class "Default")
      (node (ref "B1") (pin "2") (pinfunction "2_2") (pintype "bidirectional"))
    )
    (net (code "77") (name "unconnected-(B1-Pad3)") (class "Default")
      (node (ref "B1") (pin "3") (pinfunction "3_3") (pintype "bidirectional"))
    )
    (net (code "78") (name "unconnected-(B2-Pad1)") (class "Default")
      (node (ref "B2") (pin "1") (pinfunction "1_1") (pintype "bidirectional"))
    )
    (net (code "79") (name "unconnected-(B2-Pad3)") (class "Default")
      (node (ref "B2") (pin "3") (pinfunction "3_3") (pintype "bidirectional"))
    )
    (net (code "80") (name "unconnected-(B3-Pad1)") (class "Default")
      (node (ref "B3") (pin "1") (pinfunction "1_1") (pintype "bidirectional"))
    )
    (net (code "81") (name "unconnected-(B3-Pad4)") (class "Default")
      (node (ref "B3") (pin "4") (pinfunction "4_4") (pintype "bidirectional"))
    )
    (net (code "82") (name "unconnected-(B4-Pad2)") (class "Default")
      (node (ref "B4") (pin "2") (pinfunction "2_2") (pintype "bidirectional"))
    )
    (net (code "83") (name "unconnected-(B4-Pad3)") (class "Default")
      (node (ref "B4") (pin "3") (pinfunction "3_3") (pintype "bidirectional"))
    )
    (net (code "84") (name "unconnected-(D1-DP-Pad9)") (class "Default")
      (node (ref "D1") (pin "9") (pinfunction "DP_9") (pintype "bidirectional"))
    )
    (net (code "85") (name "unconnected-(D1-NO1-Pad3)") (class "Default")
      (node (ref "D1") (pin "3") (pinfunction "NO1_3") (pintype "bidirectional"))
    )
    (net (code "86") (name "unconnected-(D1-NO2-Pad5)") (class "Default")
      (node (ref "D1") (pin "5") (pinfunction "NO2_5") (pintype "bidirectional"))
    )
    (net (code "87") (name "unconnected-(D1-NO3-Pad6)") (class "Default")
      (node (ref "D1") (pin "6") (pinfunction "NO3_6") (pintype "bidirectional"))
    )
    (net (code "88") (name "unconnected-(D1-NO4-Pad11)") (class "Default")
      (node (ref "D1") (pin "11") (pinfunction "NO4_11") (pintype "bidirectional"))
    )
    (net (code "89") (name "unconnected-(D2-DP-Pad9)") (class "Default")
      (node (ref "D2") (pin "9") (pinfunction "DP_9") (pintype "bidirectional"))
    )
    (net (code "90") (name "unconnected-(D2-NO1-Pad3)") (class "Default")
      (node (ref "D2") (pin "3") (pinfunction "NO1_3") (pintype "bidirectional"))
    )
    (net (code "91") (name "unconnected-(D2-NO2-Pad5)") (class "Default")
      (node (ref "D2") (pin "5") (pinfunction "NO2_5") (pintype "bidirectional"))
    )
    (net (code "92") (name "unconnected-(D2-NO3-Pad6)") (class "Default")
      (node (ref "D2") (pin "6") (pinfunction "NO3_6") (pintype "bidirectional"))
    )
    (net (code "93") (name "unconnected-(D2-NO4-Pad11)") (class "Default")
      (node (ref "D2") (pin "11") (pinfunction "NO4_11") (pintype "bidirectional"))
    )
    (net (code "94") (name "unconnected-(D3-DP-Pad9)") (class "Default")
      (node (ref "D3") (pin "9") (pinfunction "DP_9") (pintype "bidirectional"))
    )
    (net (code "95") (name "unconnected-(D3-NO1-Pad3)") (class "Default")
      (node (ref "D3") (pin "3") (pinfunction "NO1_3") (pintype "bidirectional"))
    )
    (net (code "96") (name "unconnected-(D3-NO2-Pad5)") (class "Default")
      (node (ref "D3") (pin "5") (pinfunction "NO2_5") (pintype "bidirectional"))
    )
    (net (code "97") (name "unconnected-(D3-NO3-Pad6)") (class "Default")
      (node (ref "D3") (pin "6") (pinfunction "NO3_6") (pintype "bidirectional"))
    )
    (net (code "98") (name "unconnected-(D3-NO4-Pad11)") (class "Default")
      (node (ref "D3") (pin "11") (pinfunction "NO4_11") (pintype "bidirectional"))
    )
    (net (code "99") (name "unconnected-(D4-DP-Pad9)") (class "Default")
      (node (ref "D4") (pin "9") (pinfunction "DP_9") (pintype "bidirectional"))
    )
    (net (code "100") (name "unconnected-(D4-NO1-Pad3)") (class "Default")
      (node (ref "D4") (pin "3") (pinfunction "NO1_3") (pintype "bidirectional"))
    )
    (net (code "101") (name "unconnected-(D4-NO2-Pad5)") (class "Default")
      (node (ref "D4") (pin "5") (pinfunction "NO2_5") (pintype "bidirectional"))
    )
    (net (code "102") (name "unconnected-(D4-NO3-Pad6)") (class "Default")
      (node (ref "D4") (pin "6") (pinfunction "NO3_6") (pintype "bidirectional"))
    )
    (net (code "103") (name "unconnected-(D4-NO4-Pad11)") (class "Default")
      (node (ref "D4") (pin "11") (pinfunction "NO4_11") (pintype "bidirectional"))
    )
    (net (code "104") (name "unconnected-(IC6A-QH*-Pad9)") (class "Default")
      (node (ref "IC6") (pin "9") (pinfunction "QH*_9") (pintype "tri_state"))
    )
    (net (code "105") (name "unconnected-(SV1-Pad3)") (class "Default")
      (node (ref "SV1") (pin "3") (pinfunction "3_3") (pintype "passive"))
    )
    (net (code "106") (name "unconnected-(SV1-Pad4)") (class "Default")
      (node (ref "SV1") (pin "4") (pinfunction "4_4") (pintype "passive"))
    )
    (net (code "107") (name "unconnected-(SV1-Pad5)") (class "Default")
      (node (ref "SV1") (pin "5") (pinfunction "5_5") (pintype "passive"))
    )
    (net (code "108") (name "unconnected-(SV1-Pad6)") (class "Default")
      (node (ref "SV1") (pin "6") (pinfunction "6_6") (pintype "passive"))
    )
  )
)
